# zumo_lidar_01.net
KiCad netlist of a schematic drawn in EAGLE
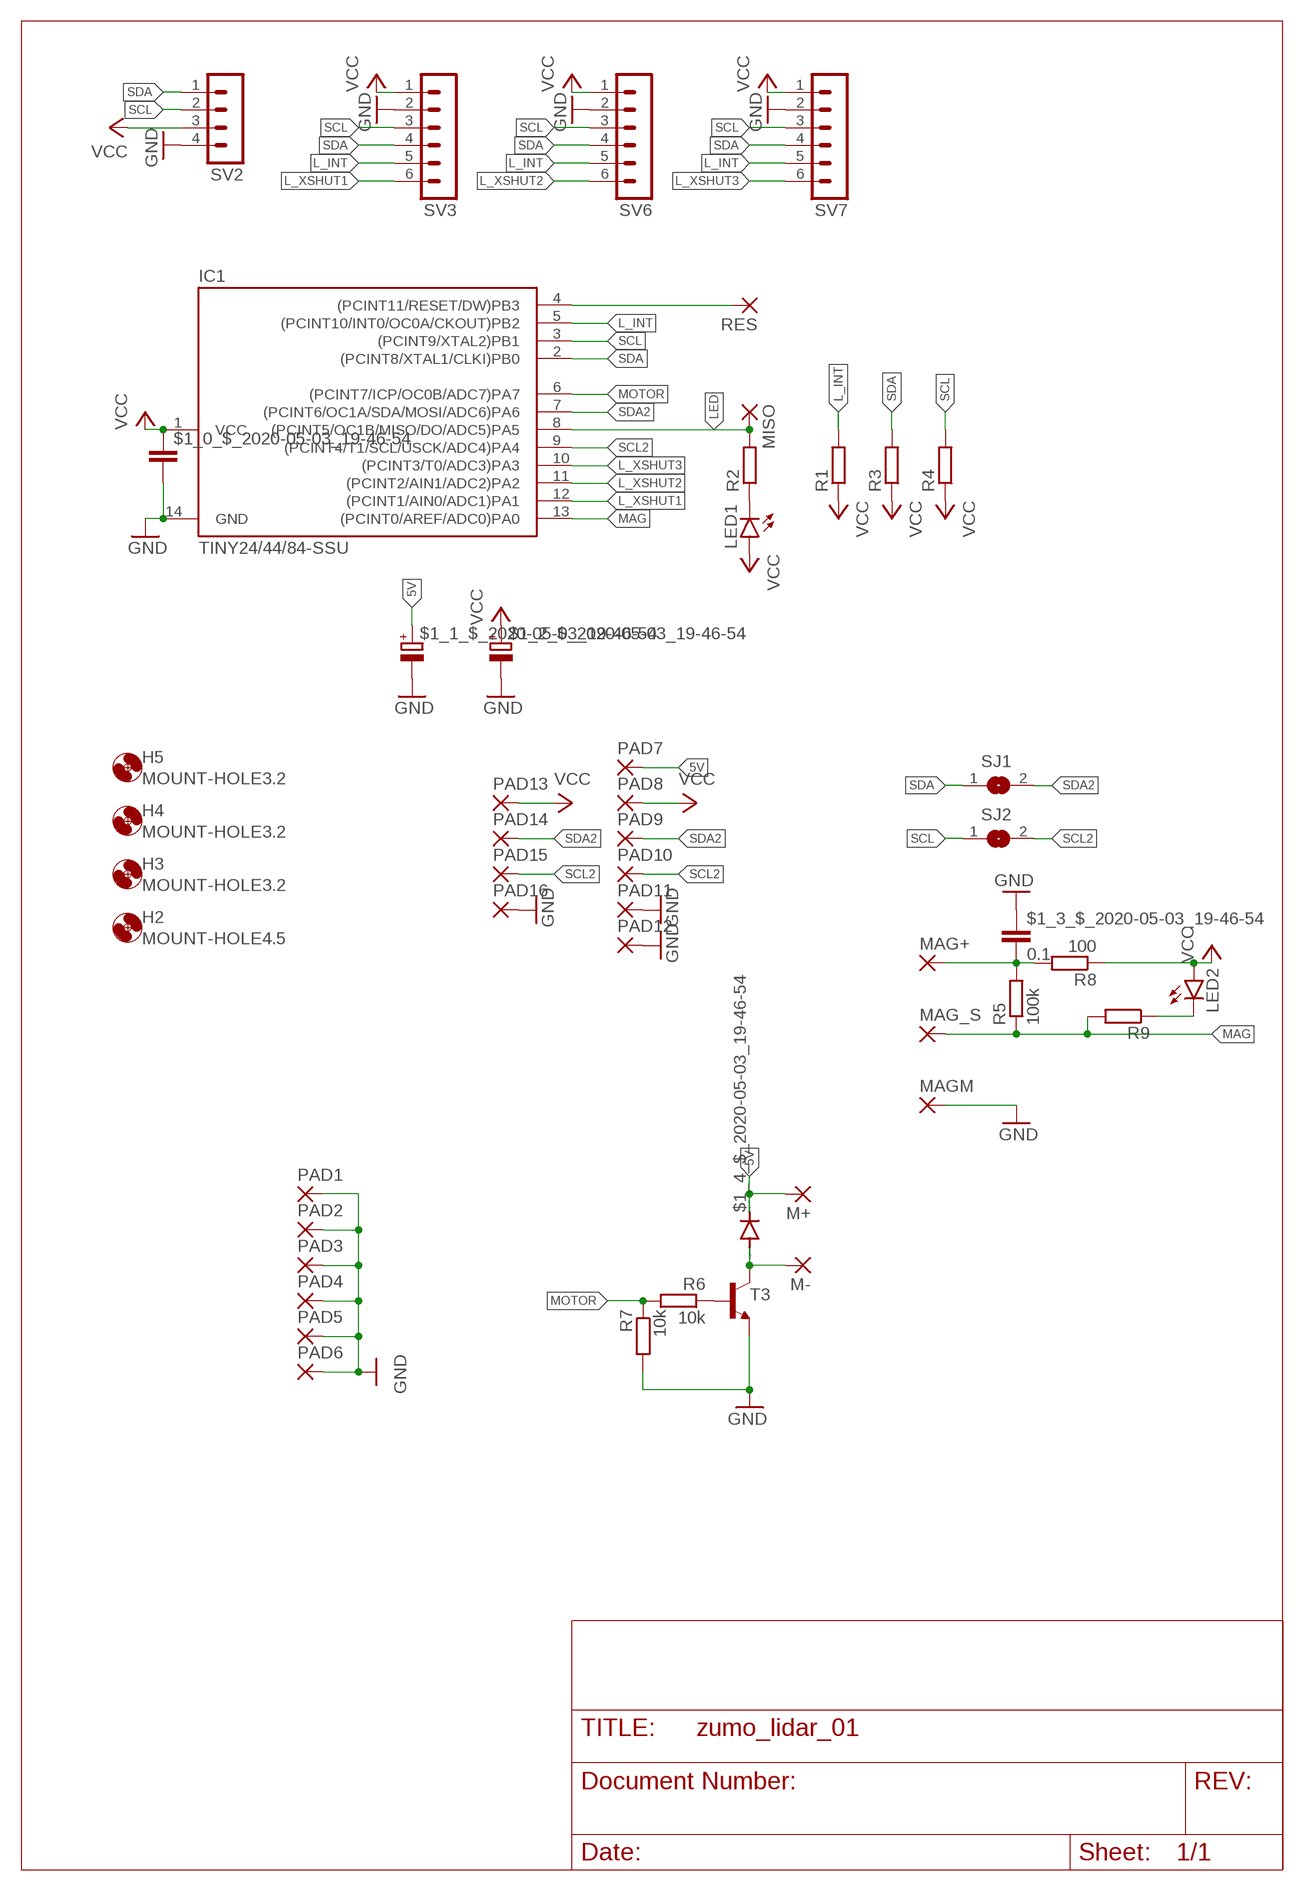
[diagram p0: schematic, sheet 1]

(export (version "E")
  (design (tool "Eeschema 10.0.6"))
  (components
    (comp (ref "$1_0_$_2020-05-03_19-46-54")
      (value "C-EUC0805")
      (footprint "eagle-import:C0805")
      (libsource (lib "eagle-import") (part "C-EUC0805"))
    )
    (comp (ref "$1_1_$_2020-05-03_19-46-54")
      (value "CPOL-EUSMCC")
      (footprint "eagle-import:SMC_C")
      (libsource (lib "eagle-import") (part "CPOL-EUSMCC"))
    )
    (comp (ref "$1_2_$_2020-05-03_19-46-54")
      (value "CPOL-EUSMCC")
      (footprint "eagle-import:SMC_C")
      (libsource (lib "eagle-import") (part "CPOL-EUSMCC"))
    )
    (comp (ref "$1_3_$_2020-05-03_19-46-54")
      (value "0.1")
      (footprint "eagle-import:C0805")
      (libsource (lib "eagle-import") (part "C-EUC0805"))
    )
    (comp (ref "$1_4_$_2020-05-03_19-46-54")
      (value "DIODE-MINIMELF")
      (footprint "eagle-import:MINIMELF")
      (libsource (lib "eagle-import") (part "DIODE-MINIMELF"))
    )
    (comp (ref "H2")
      (value "MOUNT-HOLE4.5")
      (footprint "eagle-import:4,5")
      (libsource (lib "eagle-import") (part "MOUNT-HOLE4.5"))
    )
    (comp (ref "H3")
      (value "MOUNT-HOLE3.2")
      (footprint "eagle-import:3,2")
      (libsource (lib "eagle-import") (part "MOUNT-HOLE3.2"))
    )
    (comp (ref "H4")
      (value "MOUNT-HOLE3.2")
      (footprint "eagle-import:3,2")
      (libsource (lib "eagle-import") (part "MOUNT-HOLE3.2"))
    )
    (comp (ref "H5")
      (value "MOUNT-HOLE3.2")
      (footprint "eagle-import:3,2")
      (libsource (lib "eagle-import") (part "MOUNT-HOLE3.2"))
    )
    (comp (ref "IC1")
      (value "TINY24/44/84-SSU")
      (footprint "eagle-import:SOIC14")
      (libsource (lib "eagle-import") (part "TINY24/44/84-SSU"))
    )
    (comp (ref "LED1")
      (value "LEDSML0805")
      (footprint "eagle-import:SML0805")
      (libsource (lib "eagle-import") (part "LEDSML0805"))
    )
    (comp (ref "LED2")
      (value "LEDSML0805")
      (footprint "eagle-import:SML0805")
      (libsource (lib "eagle-import") (part "LEDSML0805"))
    )
    (comp (ref "M+")
      (value "1,6/0,8")
      (footprint "eagle-import:1,6_0,8")
      (libsource (lib "eagle-import") (part "1,6/0,8"))
    )
    (comp (ref "M-")
      (value "1,6/0,8")
      (footprint "eagle-import:1,6_0,8")
      (libsource (lib "eagle-import") (part "1,6/0,8"))
    )
    (comp (ref "MAG+")
      (value "1,6/0,8")
      (footprint "eagle-import:1,6_0,8")
      (libsource (lib "eagle-import") (part "1,6/0,8"))
    )
    (comp (ref "MAGM")
      (value "1,6/0,8")
      (footprint "eagle-import:1,6_0,8")
      (libsource (lib "eagle-import") (part "1,6/0,8"))
    )
    (comp (ref "MAG_S")
      (value "1,6/0,8")
      (footprint "eagle-import:1,6_0,8")
      (libsource (lib "eagle-import") (part "1,6/0,8"))
    )
    (comp (ref "MISO")
      (value "1,6/0,8")
      (footprint "eagle-import:1,6_0,8")
      (libsource (lib "eagle-import") (part "1,6/0,8"))
    )
    (comp (ref "PAD1")
      (value "2,54/1,1")
      (footprint "eagle-import:2,54_1,1")
      (libsource (lib "eagle-import") (part "2,54/1,1"))
    )
    (comp (ref "PAD2")
      (value "2,54/1,1")
      (footprint "eagle-import:2,54_1,1")
      (libsource (lib "eagle-import") (part "2,54/1,1"))
    )
    (comp (ref "PAD3")
      (value "2,54/1,1")
      (footprint "eagle-import:2,54_1,1")
      (libsource (lib "eagle-import") (part "2,54/1,1"))
    )
    (comp (ref "PAD4")
      (value "2,54/1,1")
      (footprint "eagle-import:2,54_1,1")
      (libsource (lib "eagle-import") (part "2,54/1,1"))
    )
    (comp (ref "PAD5")
      (value "2,54/1,1")
      (footprint "eagle-import:2,54_1,1")
      (libsource (lib "eagle-import") (part "2,54/1,1"))
    )
    (comp (ref "PAD6")
      (value "2,54/1,1")
      (footprint "eagle-import:2,54_1,1")
      (libsource (lib "eagle-import") (part "2,54/1,1"))
    )
    (comp (ref "PAD7")
      (value "1,6/0,8")
      (footprint "eagle-import:1,6_0,8")
      (libsource (lib "eagle-import") (part "1,6/0,8"))
    )
    (comp (ref "PAD8")
      (value "1,6/0,8")
      (footprint "eagle-import:1,6_0,8")
      (libsource (lib "eagle-import") (part "1,6/0,8"))
    )
    (comp (ref "PAD9")
      (value "1,6/0,8")
      (footprint "eagle-import:1,6_0,8")
      (libsource (lib "eagle-import") (part "1,6/0,8"))
    )
    (comp (ref "PAD10")
      (value "1,6/0,8")
      (footprint "eagle-import:1,6_0,8")
      (libsource (lib "eagle-import") (part "1,6/0,8"))
    )
    (comp (ref "PAD11")
      (value "1,6/0,8")
      (footprint "eagle-import:1,6_0,8")
      (libsource (lib "eagle-import") (part "1,6/0,8"))
    )
    (comp (ref "PAD12")
      (value "1,6/0,8")
      (footprint "eagle-import:1,6_0,8")
      (libsource (lib "eagle-import") (part "1,6/0,8"))
    )
    (comp (ref "PAD13")
      (value "1,6/0,8")
      (footprint "eagle-import:1,6_0,8")
      (libsource (lib "eagle-import") (part "1,6/0,8"))
    )
    (comp (ref "PAD14")
      (value "1,6/0,8")
      (footprint "eagle-import:1,6_0,8")
      (libsource (lib "eagle-import") (part "1,6/0,8"))
    )
    (comp (ref "PAD15")
      (value "1,6/0,8")
      (footprint "eagle-import:1,6_0,8")
      (libsource (lib "eagle-import") (part "1,6/0,8"))
    )
    (comp (ref "PAD16")
      (value "1,6/0,8")
      (footprint "eagle-import:1,6_0,8")
      (libsource (lib "eagle-import") (part "1,6/0,8"))
    )
    (comp (ref "R1")
      (value "R-EU_M0805")
      (footprint "eagle-import:M0805")
      (libsource (lib "eagle-import") (part "rcl_334_R-EU_M0805"))
    )
    (comp (ref "R2")
      (value "R-EU_M0805")
      (footprint "eagle-import:M0805")
      (libsource (lib "eagle-import") (part "rcl_334_R-EU_M0805"))
    )
    (comp (ref "R3")
      (value "R-EU_M0805")
      (footprint "eagle-import:M0805")
      (libsource (lib "eagle-import") (part "rcl_334_R-EU_M0805"))
    )
    (comp (ref "R4")
      (value "R-EU_M0805")
      (footprint "eagle-import:M0805")
      (libsource (lib "eagle-import") (part "rcl_334_R-EU_M0805"))
    )
    (comp (ref "R5")
      (value "100k")
      (footprint "eagle-import:M0805")
      (libsource (lib "eagle-import") (part "rcl_334_R-EU_M0805"))
    )
    (comp (ref "R6")
      (value "10k")
      (footprint "eagle-import:R0805")
      (libsource (lib "eagle-import") (part "R-EU_R0805"))
    )
    (comp (ref "R7")
      (value "10k")
      (footprint "eagle-import:R0805")
      (libsource (lib "eagle-import") (part "R-EU_R0805"))
    )
    (comp (ref "R8")
      (value "100")
      (footprint "eagle-import:M0805")
      (libsource (lib "eagle-import") (part "rcl_334_R-EU_M0805"))
    )
    (comp (ref "R9")
      (value "R-EU_M0805")
      (footprint "eagle-import:M0805")
      (libsource (lib "eagle-import") (part "rcl_334_R-EU_M0805"))
    )
    (comp (ref "RES")
      (value "1,6/0,8")
      (footprint "eagle-import:1,6_0,8")
      (libsource (lib "eagle-import") (part "1,6/0,8"))
    )
    (comp (ref "SJ1") (value "SJ") (footprint "eagle-import:SJ") (libsource (lib "eagle-import") (part "SJ")))
    (comp (ref "SJ2") (value "SJ") (footprint "eagle-import:SJ") (libsource (lib "eagle-import") (part "SJ")))
    (comp (ref "SV2")
      (value "MA04-1")
      (footprint "eagle-import:MA04-1")
      (libsource (lib "eagle-import") (part "MA04-1"))
    )
    (comp (ref "SV3")
      (value "MA06-1")
      (footprint "eagle-import:MA06-1")
      (libsource (lib "eagle-import") (part "MA06-1"))
    )
    (comp (ref "SV6")
      (value "MA06-1")
      (footprint "eagle-import:MA06-1")
      (libsource (lib "eagle-import") (part "MA06-1"))
    )
    (comp (ref "SV7")
      (value "MA06-1")
      (footprint "eagle-import:MA06-1")
      (libsource (lib "eagle-import") (part "MA06-1"))
    )
    (comp (ref "T3")
      (value "BC817-16-NPN-SOT23-BEC")
      (footprint "eagle-import:SOT23-BEC")
      (libsource (lib "eagle-import") (part "-NPN-SOT23-BECBC817-16"))
    )
  )
  (nets
    (net (code "1") (name "5V") (class "Default")
      (node (ref "$1_1_$_2020-05-03_19-46-54") (pin "+") (pinfunction "+_+") (pintype "passive"))
      (node (ref "$1_4_$_2020-05-03_19-46-54") (pin "C") (pinfunction "C_C") (pintype "passive"))
      (node (ref "M+") (pin "1") (pinfunction "P_1") (pintype "passive"))
      (node (ref "PAD7") (pin "1") (pinfunction "P_1") (pintype "passive"))
    )
    (net (code "2") (name "GND") (class "Default")
      (node (ref "$1_0_$_2020-05-03_19-46-54") (pin "2") (pinfunction "2_2") (pintype "passive"))
      (node (ref "$1_1_$_2020-05-03_19-46-54") (pin "-") (pinfunction "-_-") (pintype "passive"))
      (node (ref "$1_2_$_2020-05-03_19-46-54") (pin "-") (pinfunction "-_-") (pintype "passive"))
      (node (ref "$1_3_$_2020-05-03_19-46-54") (pin "1") (pinfunction "1_1") (pintype "passive"))
      (node (ref "IC1") (pin "14") (pinfunction "GND_14") (pintype "power_in"))
      (node (ref "MAGM") (pin "1") (pinfunction "P_1") (pintype "passive"))
      (node (ref "PAD1") (pin "1") (pinfunction "P_1") (pintype "passive"))
      (node (ref "PAD11") (pin "1") (pinfunction "P_1") (pintype "passive"))
      (node (ref "PAD12") (pin "1") (pinfunction "P_1") (pintype "passive"))
      (node (ref "PAD16") (pin "1") (pinfunction "P_1") (pintype "passive"))
      (node (ref "PAD2") (pin "1") (pinfunction "P_1") (pintype "passive"))
      (node (ref "PAD3") (pin "1") (pinfunction "P_1") (pintype "passive"))
      (node (ref "PAD4") (pin "1") (pinfunction "P_1") (pintype "passive"))
      (node (ref "PAD5") (pin "1") (pinfunction "P_1") (pintype "passive"))
      (node (ref "PAD6") (pin "1") (pinfunction "P_1") (pintype "passive"))
      (node (ref "R7") (pin "2") (pinfunction "2_2") (pintype "passive"))
      (node (ref "SV2") (pin "4") (pinfunction "4_4") (pintype "passive"))
      (node (ref "SV3") (pin "2") (pinfunction "2_2") (pintype "passive"))
      (node (ref "SV6") (pin "2") (pinfunction "2_2") (pintype "passive"))
      (node (ref "SV7") (pin "2") (pinfunction "2_2") (pintype "passive"))
      (node (ref "T3") (pin "E") (pinfunction "E_E") (pintype "passive"))
    )
    (net (code "3") (name "LED") (class "Default")
      (node (ref "IC1") (pin "8") (pinfunction "(PCINT5/OC1B/MISO/DO/ADC5)PA5_8") (pintype "bidirectional"))
      (node (ref "MISO") (pin "1") (pinfunction "P_1") (pintype "passive"))
      (node (ref "R2") (pin "2") (pinfunction "2_2") (pintype "passive"))
    )
    (net (code "4") (name "L_INT") (class "Default")
      (node (ref "IC1") (pin "5") (pinfunction "(PCINT10/INT0/OC0A/CKOUT)PB2_5") (pintype "bidirectional"))
      (node (ref "R1") (pin "2") (pinfunction "2_2") (pintype "passive"))
      (node (ref "SV3") (pin "5") (pinfunction "5_5") (pintype "passive"))
      (node (ref "SV6") (pin "5") (pinfunction "5_5") (pintype "passive"))
      (node (ref "SV7") (pin "5") (pinfunction "5_5") (pintype "passive"))
    )
    (net (code "5") (name "L_XSHUT1") (class "Default")
      (node (ref "IC1") (pin "12") (pinfunction "(PCINT1/AIN0/ADC1)PA1_12") (pintype "bidirectional"))
      (node (ref "SV3") (pin "6") (pinfunction "6_6") (pintype "passive"))
    )
    (net (code "6") (name "L_XSHUT2") (class "Default")
      (node (ref "IC1") (pin "11") (pinfunction "(PCINT2/AIN1/ADC2)PA2_11") (pintype "bidirectional"))
      (node (ref "SV6") (pin "6") (pinfunction "6_6") (pintype "passive"))
    )
    (net (code "7") (name "L_XSHUT3") (class "Default")
      (node (ref "IC1") (pin "10") (pinfunction "(PCINT3/T0/ADC3)PA3_10") (pintype "bidirectional"))
      (node (ref "SV7") (pin "6") (pinfunction "6_6") (pintype "passive"))
    )
    (net (code "8") (name "MAG") (class "Default")
      (node (ref "IC1") (pin "13") (pinfunction "(PCINT0/AREF/ADC0)PA0_13") (pintype "bidirectional"))
      (node (ref "MAG_S") (pin "1") (pinfunction "P_1") (pintype "passive"))
      (node (ref "R5") (pin "1") (pinfunction "1_1") (pintype "passive"))
      (node (ref "R9") (pin "2") (pinfunction "2_2") (pintype "passive"))
    )
    (net (code "9") (name "MOTOR") (class "Default")
      (node (ref "IC1") (pin "6") (pinfunction "(PCINT7/ICP/OC0B/ADC7)PA7_6") (pintype "bidirectional"))
      (node (ref "R6") (pin "2") (pinfunction "2_2") (pintype "passive"))
      (node (ref "R7") (pin "1") (pinfunction "1_1") (pintype "passive"))
    )
    (net (code "10") (name "Net-(IC1-(PCINT11{slash}RESET{slash}DW)PB3)") (class "Default")
      (node (ref "IC1") (pin "4") (pinfunction "(PCINT11/RESET/DW)PB3_4") (pintype "bidirectional"))
      (node (ref "RES") (pin "1") (pinfunction "P_1") (pintype "passive"))
    )
    (net (code "11") (name "Net-(LED1-PadC)") (class "Default")
      (node (ref "LED1") (pin "C") (pinfunction "C_C") (pintype "passive"))
      (node (ref "R2") (pin "1") (pinfunction "1_1") (pintype "passive"))
    )
    (net (code "12") (name "Net-(LED2-PadC)") (class "Default")
      (node (ref "LED2") (pin "C") (pinfunction "C_C") (pintype "passive"))
      (node (ref "R9") (pin "1") (pinfunction "1_1") (pintype "passive"))
    )
    (net (code "13") (name "Net-(M--P)") (class "Default")
      (node (ref "$1_4_$_2020-05-03_19-46-54") (pin "A") (pinfunction "A_A") (pintype "passive"))
      (node (ref "M-") (pin "1") (pinfunction "P_1") (pintype "passive"))
      (node (ref "T3") (pin "C") (pinfunction "C_C") (pintype "passive"))
    )
    (net (code "14") (name "Net-(MAG+-P)") (class "Default")
      (node (ref "$1_3_$_2020-05-03_19-46-54") (pin "2") (pinfunction "2_2") (pintype "passive"))
      (node (ref "MAG+") (pin "1") (pinfunction "P_1") (pintype "passive"))
      (node (ref "R5") (pin "2") (pinfunction "2_2") (pintype "passive"))
      (node (ref "R8") (pin "2") (pinfunction "2_2") (pintype "passive"))
    )
    (net (code "15") (name "Net-(R6-Pad1)") (class "Default")
      (node (ref "R6") (pin "1") (pinfunction "1_1") (pintype "passive"))
      (node (ref "T3") (pin "B") (pinfunction "B_B") (pintype "passive"))
    )
    (net (code "16") (name "SCL") (class "Default")
      (node (ref "IC1") (pin "3") (pinfunction "(PCINT9/XTAL2)PB1_3") (pintype "bidirectional"))
      (node (ref "R4") (pin "2") (pinfunction "2_2") (pintype "passive"))
      (node (ref "SJ2") (pin "1") (pinfunction "1_1") (pintype "passive"))
      (node (ref "SV2") (pin "2") (pinfunction "2_2") (pintype "passive"))
      (node (ref "SV3") (pin "3") (pinfunction "3_3") (pintype "passive"))
      (node (ref "SV6") (pin "3") (pinfunction "3_3") (pintype "passive"))
      (node (ref "SV7") (pin "3") (pinfunction "3_3") (pintype "passive"))
    )
    (net (code "17") (name "SCL2") (class "Default")
      (node (ref "IC1") (pin "9") (pinfunction "(PCINT4/T1/SCL/USCK/ADC4)PA4_9") (pintype "bidirectional"))
      (node (ref "PAD10") (pin "1") (pinfunction "P_1") (pintype "passive"))
      (node (ref "PAD15") (pin "1") (pinfunction "P_1") (pintype "passive"))
      (node (ref "SJ2") (pin "2") (pinfunction "2_2") (pintype "passive"))
    )
    (net (code "18") (name "SDA") (class "Default")
      (node (ref "IC1") (pin "2") (pinfunction "(PCINT8/XTAL1/CLKI)PB0_2") (pintype "bidirectional"))
      (node (ref "R3") (pin "2") (pinfunction "2_2") (pintype "passive"))
      (node (ref "SJ1") (pin "1") (pinfunction "1_1") (pintype "passive"))
      (node (ref "SV2") (pin "1") (pinfunction "1_1") (pintype "passive"))
      (node (ref "SV3") (pin "4") (pinfunction "4_4") (pintype "passive"))
      (node (ref "SV6") (pin "4") (pinfunction "4_4") (pintype "passive"))
      (node (ref "SV7") (pin "4") (pinfunction "4_4") (pintype "passive"))
    )
    (net (code "19") (name "SDA2") (class "Default")
      (node (ref "IC1") (pin "7") (pinfunction "(PCINT6/OC1A/SDA/MOSI/ADC6)PA6_7") (pintype "bidirectional"))
      (node (ref "PAD14") (pin "1") (pinfunction "P_1") (pintype "passive"))
      (node (ref "PAD9") (pin "1") (pinfunction "P_1") (pintype "passive"))
      (node (ref "SJ1") (pin "2") (pinfunction "2_2") (pintype "passive"))
    )
    (net (code "20") (name "VCC") (class "Default")
      (node (ref "$1_0_$_2020-05-03_19-46-54") (pin "1") (pinfunction "1_1") (pintype "passive"))
      (node (ref "$1_2_$_2020-05-03_19-46-54") (pin "+") (pinfunction "+_+") (pintype "passive"))
      (node (ref "IC1") (pin "1") (pinfunction "VCC_1") (pintype "power_in"))
      (node (ref "LED1") (pin "A") (pinfunction "A_A") (pintype "passive"))
      (node (ref "LED2") (pin "A") (pinfunction "A_A") (pintype "passive"))
      (node (ref "PAD13") (pin "1") (pinfunction "P_1") (pintype "passive"))
      (node (ref "PAD8") (pin "1") (pinfunction "P_1") (pintype "passive"))
      (node (ref "R1") (pin "1") (pinfunction "1_1") (pintype "passive"))
      (node (ref "R3") (pin "1") (pinfunction "1_1") (pintype "passive"))
      (node (ref "R4") (pin "1") (pinfunction "1_1") (pintype "passive"))
      (node (ref "R8") (pin "1") (pinfunction "1_1") (pintype "passive"))
      (node (ref "SV2") (pin "3") (pinfunction "3_3") (pintype "passive"))
      (node (ref "SV3") (pin "1") (pinfunction "1_1") (pintype "passive"))
      (node (ref "SV6") (pin "1") (pinfunction "1_1") (pintype "passive"))
      (node (ref "SV7") (pin "1") (pinfunction "1_1") (pintype "passive"))
    )
  )
)
